# Adafruit_Neo_Trinkey.net
KiCad netlist of a schematic drawn in EAGLE
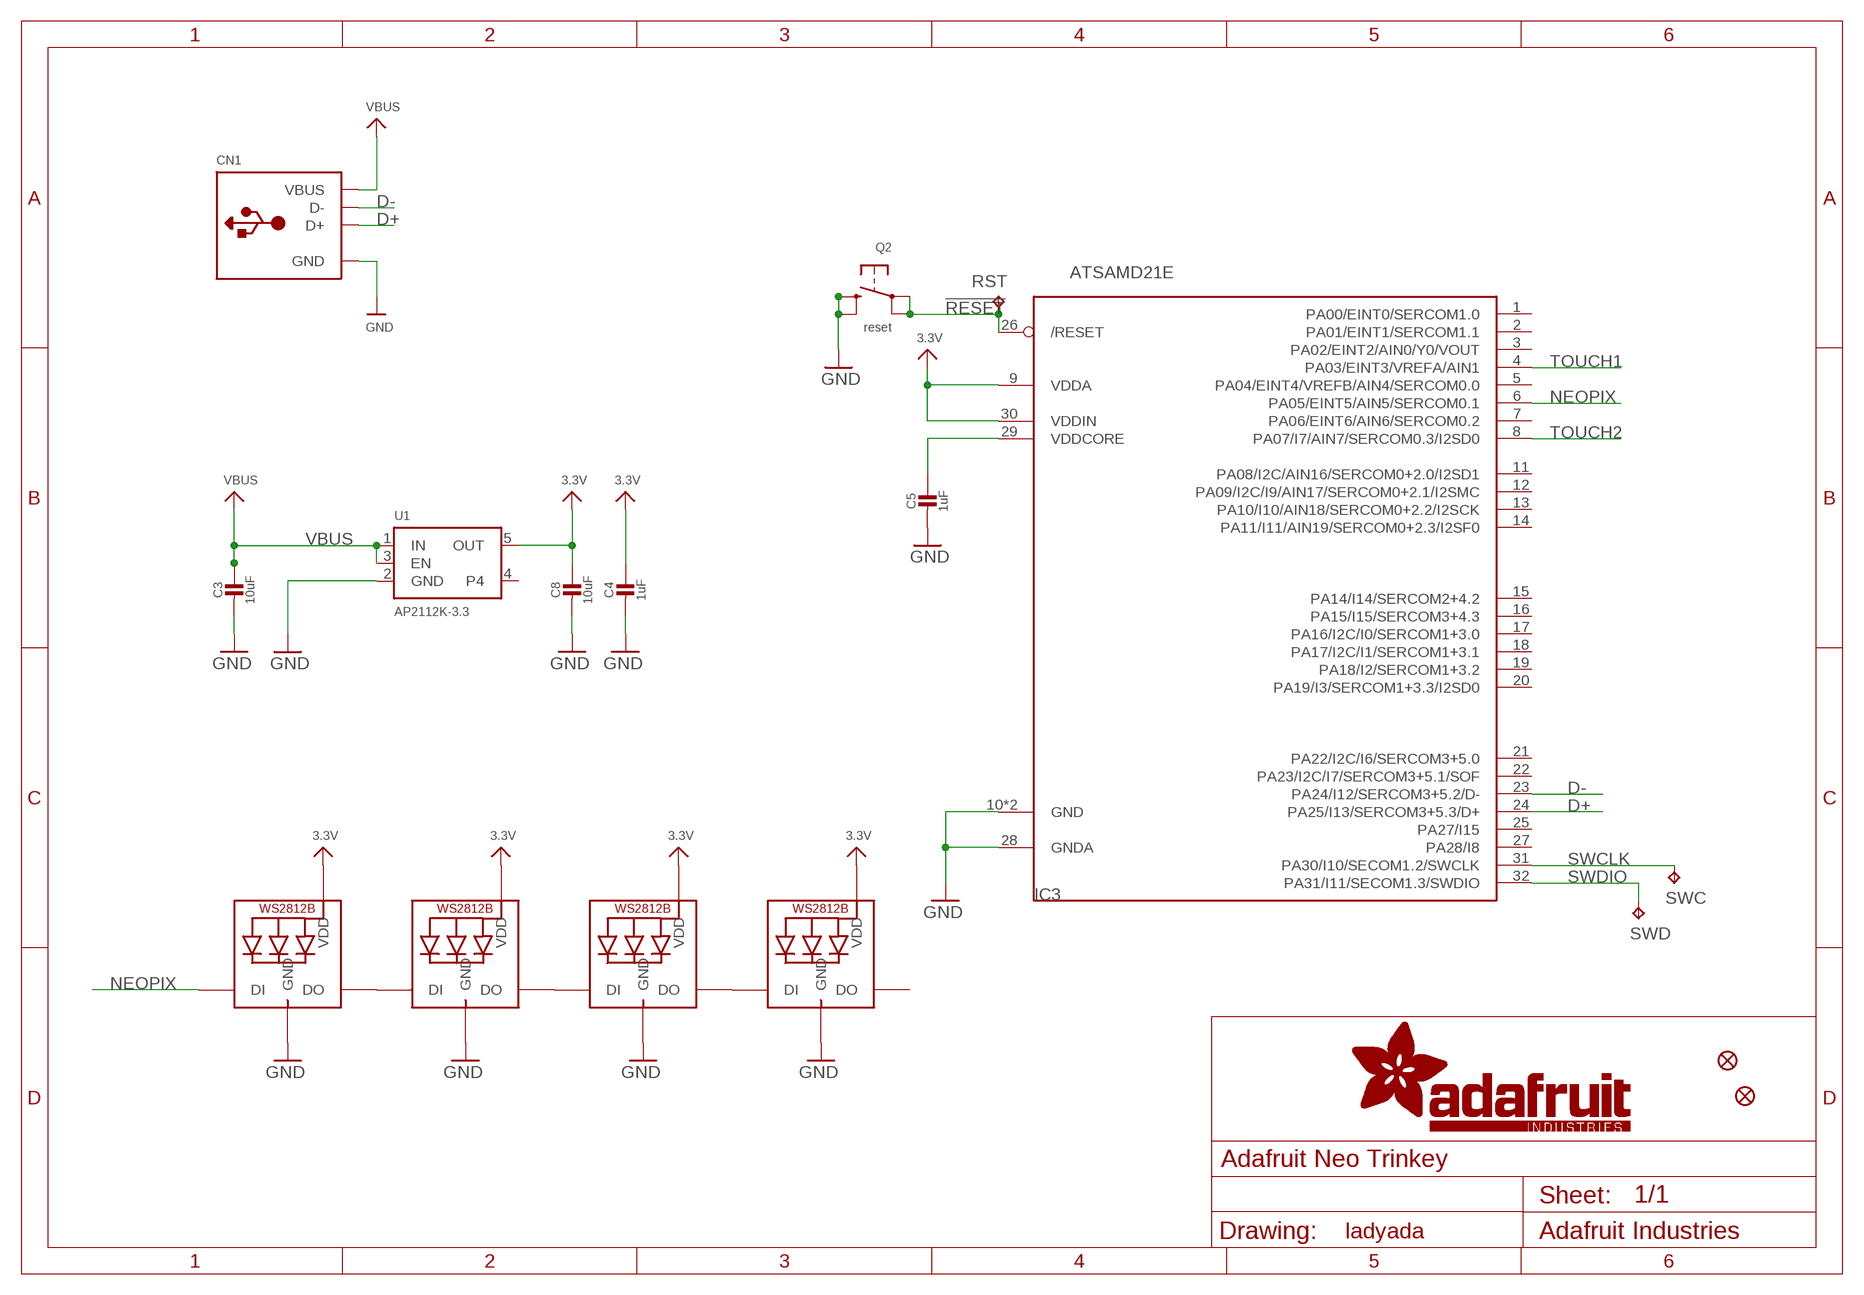
[diagram p0: schematic, sheet 1]

(export (version "E")
  (design (tool "Eeschema 10.0.6"))
  (components
    (comp (ref "C3")
      (value "10uF")
      (footprint "eagle-import:0805-NO")
      (libsource (lib "eagle-import") (part "CAP_CERAMIC0805-NOOUTLINE"))
    )
    (comp (ref "C4")
      (value "1uF")
      (footprint "eagle-import:0603-NO")
      (libsource (lib "eagle-import") (part "CAP_CERAMIC0603_NO"))
    )
    (comp (ref "C5")
      (value "1uF")
      (footprint "eagle-import:0603-NO")
      (libsource (lib "eagle-import") (part "CAP_CERAMIC0603_NO"))
    )
    (comp (ref "C8")
      (value "10uF")
      (footprint "eagle-import:0805-NO")
      (libsource (lib "eagle-import") (part "CAP_CERAMIC0805-NOOUTLINE"))
    )
    (comp (ref "CN1")
      (value "USB_TYPEAPCB")
      (footprint "eagle-import:USBA_PCB")
      (libsource (lib "eagle-import") (part "USB_TYPEAPCB"))
    )
    (comp (ref "FID1")
      (value "FIDUCIAL_1MM")
      (footprint "eagle-import:FIDUCIAL_1MM")
      (libsource (lib "eagle-import") (part "FIDUCIAL_1MM"))
    )
    (comp (ref "FID2")
      (value "FIDUCIAL_1MM")
      (footprint "eagle-import:FIDUCIAL_1MM")
      (libsource (lib "eagle-import") (part "FIDUCIAL_1MM"))
    )
    (comp (ref "IC3")
      (value "ATSAMD21E")
      (footprint "eagle-import:QFN32_5MM")
      (libsource (lib "eagle-import") (part "ATSAMD21E"))
    )
    (comp (ref "LED1")
      (value "WS2812B3535")
      (footprint "eagle-import:LED3535")
      (libsource (lib "eagle-import") (part "WS2812B3535"))
    )
    (comp (ref "LED2")
      (value "WS2812B3535")
      (footprint "eagle-import:LED3535")
      (libsource (lib "eagle-import") (part "WS2812B3535"))
    )
    (comp (ref "LED3")
      (value "WS2812B3535")
      (footprint "eagle-import:LED3535")
      (libsource (lib "eagle-import") (part "WS2812B3535"))
    )
    (comp (ref "LED4")
      (value "WS2812B3535")
      (footprint "eagle-import:LED3535")
      (libsource (lib "eagle-import") (part "WS2812B3535"))
    )
    (comp (ref "Q2")
      (value "reset")
      (footprint "eagle-import:BTN_KMR2_4.6X2.8")
      (libsource (lib "eagle-import") (part "SWITCH_TACT_SMT4.6X2.8"))
    )
    (comp (ref "RST")
      (value "TPTP16R")
      (footprint "eagle-import:TP16R")
      (libsource (lib "eagle-import") (part "TPTP16R"))
    )
    (comp (ref "SWC")
      (value "TPTP15R")
      (footprint "eagle-import:TP15R")
      (libsource (lib "eagle-import") (part "TPTP15R"))
    )
    (comp (ref "SWD")
      (value "TPTP16R")
      (footprint "eagle-import:TP16R")
      (libsource (lib "eagle-import") (part "TPTP16R"))
    )
    (comp (ref "U1")
      (value "AP2112K-3.3")
      (footprint "eagle-import:SOT23-5")
      (libsource (lib "eagle-import") (part "VREG_SOT23-5"))
    )
  )
  (nets
    (net (code "1") (name "/D+") (class "Default")
      (node (ref "CN1") (pin "USB_PLUS") (pinfunction "D+_USB_PLUS") (pintype "bidirectional"))
      (node (ref "IC3") (pin "24") (pinfunction "PA25/I13/SERCOM3+5.3/D+_24") (pintype "bidirectional"))
    )
    (net (code "2") (name "/D-") (class "Default")
      (node (ref "CN1") (pin "USB_NEG") (pinfunction "D-_USB_NEG") (pintype "bidirectional"))
      (node (ref "IC3") (pin "23") (pinfunction "PA24/I12/SERCOM3+5.2/D-_23") (pintype "bidirectional"))
    )
    (net (code "3") (name "/NEOPIX") (class "Default")
      (node (ref "IC3") (pin "6") (pinfunction "PA05/EINT5/AIN5/SERCOM0.1_6") (pintype "bidirectional"))
      (node (ref "LED1") (pin "1") (pinfunction "DI_1") (pintype "input"))
    )
    (net (code "4") (name "/SWCLK") (class "Default")
      (node (ref "IC3") (pin "31") (pinfunction "PA30/I10/SECOM1.2/SWCLK_31") (pintype "bidirectional"))
      (node (ref "SWC") (pin "TP") (pinfunction "TP_TP") (pintype "input"))
    )
    (net (code "5") (name "/SWDIO") (class "Default")
      (node (ref "IC3") (pin "32") (pinfunction "PA31/I11/SECOM1.3/SWDIO_32") (pintype "bidirectional"))
      (node (ref "SWD") (pin "TP") (pinfunction "TP_TP") (pintype "input"))
    )
    (net (code "6") (name "/TOUCH1") (class "Default")
      (node (ref "IC3") (pin "4") (pinfunction "PA03/EINT3/VREFA/AIN1_4") (pintype "bidirectional"))
    )
    (net (code "7") (name "/TOUCH2") (class "Default")
      (node (ref "IC3") (pin "8") (pinfunction "PA07/I7/AIN7/SERCOM0.3/I2SD0_8") (pintype "bidirectional"))
    )
    (net (code "8") (name "/~{RESET}") (class "Default")
      (node (ref "IC3") (pin "26") (pinfunction "/RESET_26") (pintype "bidirectional"))
      (node (ref "Q2") (pin "A") (pinfunction "P_A") (pintype "passive"))
      (node (ref "Q2") (pin "A'") (pinfunction "P1_A'") (pintype "passive"))
      (node (ref "RST") (pin "TP") (pinfunction "TP_TP") (pintype "input"))
    )
    (net (code "9") (name "3.3V") (class "Default")
      (node (ref "C4") (pin "1") (pinfunction "1_1") (pintype "passive"))
      (node (ref "C8") (pin "1") (pinfunction "1_1") (pintype "passive"))
      (node (ref "IC3") (pin "30") (pinfunction "VDDIN_30") (pintype "power_in"))
      (node (ref "IC3") (pin "9") (pinfunction "VDDA_9") (pintype "power_in"))
      (node (ref "LED1") (pin "2") (pinfunction "VDD_2") (pintype "power_in"))
      (node (ref "LED2") (pin "2") (pinfunction "VDD_2") (pintype "power_in"))
      (node (ref "LED3") (pin "2") (pinfunction "VDD_2") (pintype "power_in"))
      (node (ref "LED4") (pin "2") (pinfunction "VDD_2") (pintype "power_in"))
      (node (ref "U1") (pin "5") (pinfunction "OUT_5") (pintype "power_in"))
    )
    (net (code "10") (name "GND") (class "Default")
      (node (ref "C3") (pin "2") (pinfunction "2_2") (pintype "passive"))
      (node (ref "C4") (pin "2") (pinfunction "2_2") (pintype "passive"))
      (node (ref "C5") (pin "2") (pinfunction "2_2") (pintype "passive"))
      (node (ref "C8") (pin "2") (pinfunction "2_2") (pintype "passive"))
      (node (ref "CN1") (pin "GND") (pinfunction "GND_GND") (pintype "power_in"))
      (node (ref "IC3") (pin "10") (pinfunction "GND_10") (pintype "power_in"))
      (node (ref "IC3") (pin "28") (pinfunction "GNDA_28") (pintype "power_in"))
      (node (ref "IC3") (pin "33") (pinfunction "GND_33") (pintype "power_in"))
      (node (ref "LED1") (pin "4") (pinfunction "GND_4") (pintype "power_in"))
      (node (ref "LED2") (pin "4") (pinfunction "GND_4") (pintype "power_in"))
      (node (ref "LED3") (pin "4") (pinfunction "GND_4") (pintype "power_in"))
      (node (ref "LED4") (pin "4") (pinfunction "GND_4") (pintype "power_in"))
      (node (ref "Q2") (pin "B") (pinfunction "S_B") (pintype "passive"))
      (node (ref "Q2") (pin "B'") (pinfunction "S1_B'") (pintype "passive"))
      (node (ref "U1") (pin "2") (pinfunction "GND_2") (pintype "power_in"))
    )
    (net (code "11") (name "Net-(IC3-VDDCORE)") (class "Default")
      (node (ref "C5") (pin "1") (pinfunction "1_1") (pintype "passive"))
      (node (ref "IC3") (pin "29") (pinfunction "VDDCORE_29") (pintype "power_in"))
    )
    (net (code "12") (name "Net-(LED1-DO)") (class "Default")
      (node (ref "LED1") (pin "3") (pinfunction "DO_3") (pintype "output"))
      (node (ref "LED2") (pin "1") (pinfunction "DI_1") (pintype "input"))
    )
    (net (code "13") (name "Net-(LED2-DO)") (class "Default")
      (node (ref "LED2") (pin "3") (pinfunction "DO_3") (pintype "output"))
      (node (ref "LED3") (pin "1") (pinfunction "DI_1") (pintype "input"))
    )
    (net (code "14") (name "Net-(LED3-DO)") (class "Default")
      (node (ref "LED3") (pin "3") (pinfunction "DO_3") (pintype "output"))
      (node (ref "LED4") (pin "1") (pinfunction "DI_1") (pintype "input"))
    )
    (net (code "15") (name "VBUS") (class "Default")
      (node (ref "C3") (pin "1") (pinfunction "1_1") (pintype "passive"))
      (node (ref "CN1") (pin "VCC") (pinfunction "VBUS_VCC") (pintype "power_in"))
      (node (ref "U1") (pin "1") (pinfunction "IN_1") (pintype "power_in"))
      (node (ref "U1") (pin "3") (pinfunction "EN_3") (pintype "input"))
    )
    (net (code "16") (name "unconnected-(IC3-PA00{slash}EINT0{slash}SERCOM1.0-Pad1)") (class "Default")
      (node (ref "IC3") (pin "1") (pinfunction "PA00/EINT0/SERCOM1.0_1") (pintype "bidirectional"))
    )
    (net (code "17") (name "unconnected-(IC3-PA01{slash}EINT1{slash}SERCOM1.1-Pad2)") (class "Default")
      (node (ref "IC3") (pin "2") (pinfunction "PA01/EINT1/SERCOM1.1_2") (pintype "bidirectional"))
    )
    (net (code "18") (name "unconnected-(IC3-PA02{slash}EINT2{slash}AIN0{slash}Y0{slash}VOUT-Pad3)") (class "Default")
      (node (ref "IC3") (pin "3") (pinfunction "PA02/EINT2/AIN0/Y0/VOUT_3") (pintype "bidirectional"))
    )
    (net (code "19") (name "unconnected-(IC3-PA04{slash}EINT4{slash}VREFB{slash}AIN4{slash}SERCOM0.0-Pad5)") (class "Default")
      (node (ref "IC3") (pin "5") (pinfunction "PA04/EINT4/VREFB/AIN4/SERCOM0.0_5") (pintype "bidirectional"))
    )
    (net (code "20") (name "unconnected-(IC3-PA06{slash}EINT6{slash}AIN6{slash}SERCOM0.2-Pad7)") (class "Default")
      (node (ref "IC3") (pin "7") (pinfunction "PA06/EINT6/AIN6/SERCOM0.2_7") (pintype "bidirectional"))
    )
    (net (code "21") (name "unconnected-(IC3-PA08{slash}I2C{slash}AIN16{slash}SERCOM0+2.0{slash}I2SD1-Pad11)") (class "Default")
      (node (ref "IC3") (pin "11") (pinfunction "PA08/I2C/AIN16/SERCOM0+2.0/I2SD1_11") (pintype "bidirectional"))
    )
    (net (code "22") (name "unconnected-(IC3-PA09{slash}I2C{slash}I9{slash}AIN17{slash}SERCOM0+2.1{slash}I2SMC-Pad12)") (class "Default")
      (node (ref "IC3") (pin "12") (pinfunction "PA09/I2C/I9/AIN17/SERCOM0+2.1/I2SMC_12") (pintype "bidirectional"))
    )
    (net (code "23") (name "unconnected-(IC3-PA10{slash}I10{slash}AIN18{slash}SERCOM0+2.2{slash}I2SCK-Pad13)") (class "Default")
      (node (ref "IC3") (pin "13") (pinfunction "PA10/I10/AIN18/SERCOM0+2.2/I2SCK_13") (pintype "bidirectional"))
    )
    (net (code "24") (name "unconnected-(IC3-PA11{slash}I11{slash}AIN19{slash}SERCOM0+2.3{slash}I2SF0-Pad14)") (class "Default")
      (node (ref "IC3") (pin "14") (pinfunction "PA11/I11/AIN19/SERCOM0+2.3/I2SF0_14") (pintype "bidirectional"))
    )
    (net (code "25") (name "unconnected-(IC3-PA14{slash}I14{slash}SERCOM2+4.2-Pad15)") (class "Default")
      (node (ref "IC3") (pin "15") (pinfunction "PA14/I14/SERCOM2+4.2_15") (pintype "bidirectional"))
    )
    (net (code "26") (name "unconnected-(IC3-PA15{slash}I15{slash}SERCOM3+4.3-Pad16)") (class "Default")
      (node (ref "IC3") (pin "16") (pinfunction "PA15/I15/SERCOM3+4.3_16") (pintype "bidirectional"))
    )
    (net (code "27") (name "unconnected-(IC3-PA16{slash}I2C{slash}I0{slash}SERCOM1+3.0-Pad17)") (class "Default")
      (node (ref "IC3") (pin "17") (pinfunction "PA16/I2C/I0/SERCOM1+3.0_17") (pintype "bidirectional"))
    )
    (net (code "28") (name "unconnected-(IC3-PA17{slash}I2C{slash}I1{slash}SERCOM1+3.1-Pad18)") (class "Default")
      (node (ref "IC3") (pin "18") (pinfunction "PA17/I2C/I1/SERCOM1+3.1_18") (pintype "bidirectional"))
    )
    (net (code "29") (name "unconnected-(IC3-PA18{slash}I2{slash}SERCOM1+3.2-Pad19)") (class "Default")
      (node (ref "IC3") (pin "19") (pinfunction "PA18/I2/SERCOM1+3.2_19") (pintype "bidirectional"))
    )
    (net (code "30") (name "unconnected-(IC3-PA19{slash}I3{slash}SERCOM1+3.3{slash}I2SD0-Pad20)") (class "Default")
      (node (ref "IC3") (pin "20") (pinfunction "PA19/I3/SERCOM1+3.3/I2SD0_20") (pintype "bidirectional"))
    )
    (net (code "31") (name "unconnected-(IC3-PA22{slash}I2C{slash}I6{slash}SERCOM3+5.0-Pad21)") (class "Default")
      (node (ref "IC3") (pin "21") (pinfunction "PA22/I2C/I6/SERCOM3+5.0_21") (pintype "bidirectional"))
    )
    (net (code "32") (name "unconnected-(IC3-PA23{slash}I2C{slash}I7{slash}SERCOM3+5.1{slash}SOF-Pad22)") (class "Default")
      (node (ref "IC3") (pin "22") (pinfunction "PA23/I2C/I7/SERCOM3+5.1/SOF_22") (pintype "bidirectional"))
    )
    (net (code "33") (name "unconnected-(IC3-PA27{slash}I15-Pad25)") (class "Default")
      (node (ref "IC3") (pin "25") (pinfunction "PA27/I15_25") (pintype "bidirectional"))
    )
    (net (code "34") (name "unconnected-(IC3-PA28{slash}I8-Pad27)") (class "Default")
      (node (ref "IC3") (pin "27") (pinfunction "PA28/I8_27") (pintype "bidirectional"))
    )
    (net (code "35") (name "unconnected-(LED4-DO-Pad3)") (class "Default")
      (node (ref "LED4") (pin "3") (pinfunction "DO_3") (pintype "output"))
    )
    (net (code "36") (name "unconnected-(U1-P4-Pad4)") (class "Default")
      (node (ref "U1") (pin "4") (pinfunction "P4_4") (pintype "bidirectional"))
    )
  )
)
